# fonteechaveador2.net
KiCad netlist of a schematic drawn in EAGLE
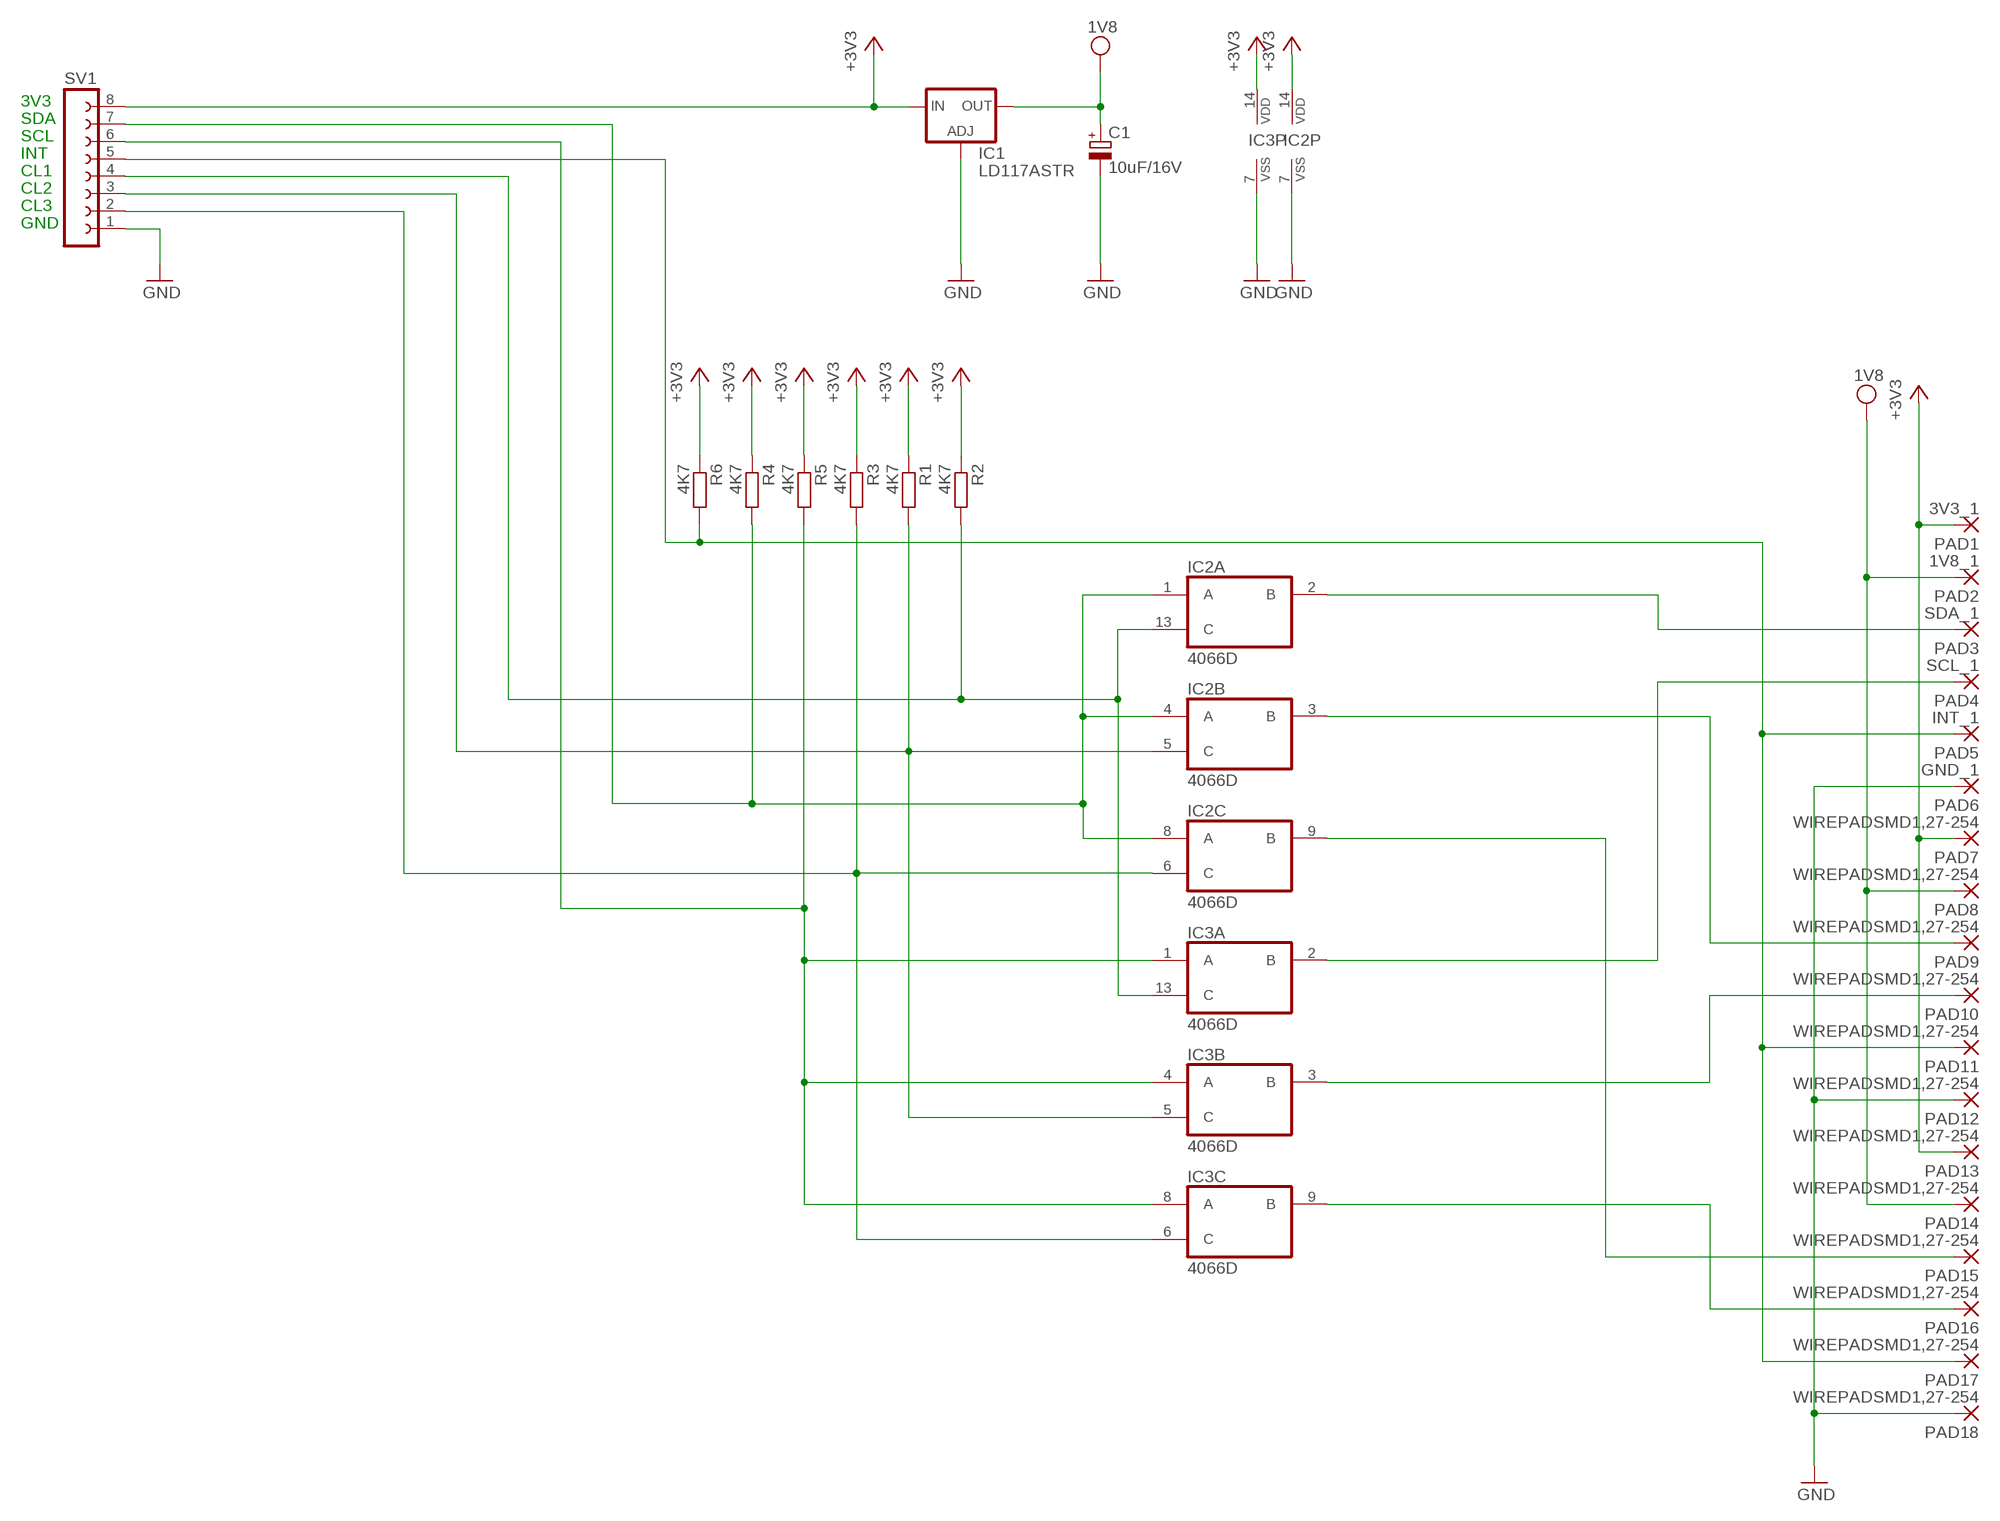
[diagram p0: schematic, sheet 1]

(export (version "E")
  (design (tool "Eeschema 10.0.6"))
  (components
    (comp (ref "C1")
      (value "10uF/16V")
      (footprint "eagle-import:140CLH-0810")
      (libsource (lib "eagle-import") (part "CPOL-EU140CLH-0810"))
    )
    (comp (ref "IC1")
      (value "LD117ASTR")
      (footprint "eagle-import:SOT223")
      (libsource (lib "eagle-import") (part "LD117A?STR"))
    )
    (comp (ref "IC2")
      (value "4066D")
      (footprint "eagle-import:SO14")
      (libsource (lib "eagle-import") (part "4066D"))
    )
    (comp (ref "IC3")
      (value "4066D")
      (footprint "eagle-import:SO14")
      (libsource (lib "eagle-import") (part "4066D"))
    )
    (comp (ref "PAD1")
      (value "3V3_1")
      (footprint "eagle-import:SMD1,27-2,54")
      (libsource (lib "eagle-import") (part "WIREPADSMD1,27-254"))
    )
    (comp (ref "PAD2")
      (value "1V8_1")
      (footprint "eagle-import:SMD1,27-2,54")
      (libsource (lib "eagle-import") (part "WIREPADSMD1,27-254"))
    )
    (comp (ref "PAD3")
      (value "SDA_1")
      (footprint "eagle-import:SMD1,27-2,54")
      (libsource (lib "eagle-import") (part "WIREPADSMD1,27-254"))
    )
    (comp (ref "PAD4")
      (value "SCL_1")
      (footprint "eagle-import:SMD1,27-2,54")
      (libsource (lib "eagle-import") (part "WIREPADSMD1,27-254"))
    )
    (comp (ref "PAD5")
      (value "INT_1")
      (footprint "eagle-import:SMD1,27-2,54")
      (libsource (lib "eagle-import") (part "WIREPADSMD1,27-254"))
    )
    (comp (ref "PAD6")
      (value "GND_1")
      (footprint "eagle-import:SMD1,27-2,54")
      (libsource (lib "eagle-import") (part "WIREPADSMD1,27-254"))
    )
    (comp (ref "PAD7")
      (value "WIREPADSMD1,27-254")
      (footprint "eagle-import:SMD1,27-2,54")
      (libsource (lib "eagle-import") (part "WIREPADSMD1,27-254"))
    )
    (comp (ref "PAD8")
      (value "WIREPADSMD1,27-254")
      (footprint "eagle-import:SMD1,27-2,54")
      (libsource (lib "eagle-import") (part "WIREPADSMD1,27-254"))
    )
    (comp (ref "PAD9")
      (value "WIREPADSMD1,27-254")
      (footprint "eagle-import:SMD1,27-2,54")
      (libsource (lib "eagle-import") (part "WIREPADSMD1,27-254"))
    )
    (comp (ref "PAD10")
      (value "WIREPADSMD1,27-254")
      (footprint "eagle-import:SMD1,27-2,54")
      (libsource (lib "eagle-import") (part "WIREPADSMD1,27-254"))
    )
    (comp (ref "PAD11")
      (value "WIREPADSMD1,27-254")
      (footprint "eagle-import:SMD1,27-2,54")
      (libsource (lib "eagle-import") (part "WIREPADSMD1,27-254"))
    )
    (comp (ref "PAD12")
      (value "WIREPADSMD1,27-254")
      (footprint "eagle-import:SMD1,27-2,54")
      (libsource (lib "eagle-import") (part "WIREPADSMD1,27-254"))
    )
    (comp (ref "PAD13")
      (value "WIREPADSMD1,27-254")
      (footprint "eagle-import:SMD1,27-2,54")
      (libsource (lib "eagle-import") (part "WIREPADSMD1,27-254"))
    )
    (comp (ref "PAD14")
      (value "WIREPADSMD1,27-254")
      (footprint "eagle-import:SMD1,27-2,54")
      (libsource (lib "eagle-import") (part "WIREPADSMD1,27-254"))
    )
    (comp (ref "PAD15")
      (value "WIREPADSMD1,27-254")
      (footprint "eagle-import:SMD1,27-2,54")
      (libsource (lib "eagle-import") (part "WIREPADSMD1,27-254"))
    )
    (comp (ref "PAD16")
      (value "WIREPADSMD1,27-254")
      (footprint "eagle-import:SMD1,27-2,54")
      (libsource (lib "eagle-import") (part "WIREPADSMD1,27-254"))
    )
    (comp (ref "PAD17")
      (value "WIREPADSMD1,27-254")
      (footprint "eagle-import:SMD1,27-2,54")
      (libsource (lib "eagle-import") (part "WIREPADSMD1,27-254"))
    )
    (comp (ref "PAD18")
      (value "WIREPADSMD1,27-254")
      (footprint "eagle-import:SMD1,27-2,54")
      (libsource (lib "eagle-import") (part "WIREPADSMD1,27-254"))
    )
    (comp (ref "R1")
      (value "4K7")
      (footprint "eagle-import:M0805")
      (libsource (lib "eagle-import") (part "R-EU_M0805"))
    )
    (comp (ref "R2")
      (value "4K7")
      (footprint "eagle-import:M0805")
      (libsource (lib "eagle-import") (part "R-EU_M0805"))
    )
    (comp (ref "R3")
      (value "4K7")
      (footprint "eagle-import:M0805")
      (libsource (lib "eagle-import") (part "R-EU_M0805"))
    )
    (comp (ref "R4")
      (value "4K7")
      (footprint "eagle-import:M0805")
      (libsource (lib "eagle-import") (part "R-EU_M0805"))
    )
    (comp (ref "R5")
      (value "4K7")
      (footprint "eagle-import:M0805")
      (libsource (lib "eagle-import") (part "R-EU_M0805"))
    )
    (comp (ref "R6")
      (value "4K7")
      (footprint "eagle-import:M0805")
      (libsource (lib "eagle-import") (part "R-EU_M0805"))
    )
    (comp (ref "SV1")
      (value "FE08-1")
      (footprint "eagle-import:FE08")
      (libsource (lib "eagle-import") (part "FE08-1"))
    )
  )
  (nets
    (net (code "1") (name "+3V3") (class "Default")
      (node (ref "IC1") (pin "3") (pinfunction "IN_3") (pintype "input"))
      (node (ref "IC2") (pin "14") (pinfunction "VDD_14") (pintype "power_in"))
      (node (ref "IC3") (pin "14") (pinfunction "VDD_14") (pintype "power_in"))
      (node (ref "PAD1") (pin "1") (pinfunction "P_1") (pintype "passive"))
      (node (ref "PAD13") (pin "1") (pinfunction "P_1") (pintype "passive"))
      (node (ref "PAD7") (pin "1") (pinfunction "P_1") (pintype "passive"))
      (node (ref "R1") (pin "1") (pinfunction "1_1") (pintype "passive"))
      (node (ref "R2") (pin "1") (pinfunction "1_1") (pintype "passive"))
      (node (ref "R3") (pin "1") (pinfunction "1_1") (pintype "passive"))
      (node (ref "R4") (pin "1") (pinfunction "1_1") (pintype "passive"))
      (node (ref "R5") (pin "1") (pinfunction "1_1") (pintype "passive"))
      (node (ref "R6") (pin "1") (pinfunction "1_1") (pintype "passive"))
      (node (ref "SV1") (pin "8") (pinfunction "8_8") (pintype "passive"))
    )
    (net (code "2") (name "1V8") (class "Default")
      (node (ref "C1") (pin "+") (pinfunction "+_+") (pintype "passive"))
      (node (ref "IC1") (pin "4") (pinfunction "OUT_4") (pintype "passive"))
      (node (ref "PAD14") (pin "1") (pinfunction "P_1") (pintype "passive"))
      (node (ref "PAD2") (pin "1") (pinfunction "P_1") (pintype "passive"))
      (node (ref "PAD8") (pin "1") (pinfunction "P_1") (pintype "passive"))
    )
    (net (code "3") (name "GND") (class "Default")
      (node (ref "C1") (pin "-") (pinfunction "-_-") (pintype "passive"))
      (node (ref "IC1") (pin "1") (pinfunction "ADJ_1") (pintype "input"))
      (node (ref "IC2") (pin "7") (pinfunction "VSS_7") (pintype "power_in"))
      (node (ref "IC3") (pin "7") (pinfunction "VSS_7") (pintype "power_in"))
      (node (ref "PAD12") (pin "1") (pinfunction "P_1") (pintype "passive"))
      (node (ref "PAD18") (pin "1") (pinfunction "P_1") (pintype "passive"))
      (node (ref "PAD6") (pin "1") (pinfunction "P_1") (pintype "passive"))
      (node (ref "SV1") (pin "1") (pinfunction "1_1") (pintype "passive"))
    )
    (net (code "4") (name "Net-(IC2A-A)") (class "Default")
      (node (ref "IC2") (pin "1") (pinfunction "A_1") (pintype "tri_state"))
      (node (ref "IC2") (pin "4") (pinfunction "A_4") (pintype "tri_state"))
      (node (ref "IC2") (pin "8") (pinfunction "A_8") (pintype "tri_state"))
      (node (ref "R4") (pin "2") (pinfunction "2_2") (pintype "passive"))
      (node (ref "SV1") (pin "7") (pinfunction "7_7") (pintype "passive"))
    )
    (net (code "5") (name "Net-(IC2A-B)") (class "Default")
      (node (ref "IC2") (pin "2") (pinfunction "B_2") (pintype "tri_state"))
      (node (ref "PAD3") (pin "1") (pinfunction "P_1") (pintype "passive"))
    )
    (net (code "6") (name "Net-(IC2A-C)") (class "Default")
      (node (ref "IC2") (pin "13") (pinfunction "C_13") (pintype "input"))
      (node (ref "IC3") (pin "13") (pinfunction "C_13") (pintype "input"))
      (node (ref "R2") (pin "2") (pinfunction "2_2") (pintype "passive"))
      (node (ref "SV1") (pin "4") (pinfunction "4_4") (pintype "passive"))
    )
    (net (code "7") (name "Net-(IC2B-B)") (class "Default")
      (node (ref "IC2") (pin "3") (pinfunction "B_3") (pintype "tri_state"))
      (node (ref "PAD9") (pin "1") (pinfunction "P_1") (pintype "passive"))
    )
    (net (code "8") (name "Net-(IC2B-C)") (class "Default")
      (node (ref "IC2") (pin "5") (pinfunction "C_5") (pintype "input"))
      (node (ref "IC3") (pin "5") (pinfunction "C_5") (pintype "input"))
      (node (ref "R1") (pin "2") (pinfunction "2_2") (pintype "passive"))
      (node (ref "SV1") (pin "3") (pinfunction "3_3") (pintype "passive"))
    )
    (net (code "9") (name "Net-(IC2C-B)") (class "Default")
      (node (ref "IC2") (pin "9") (pinfunction "B_9") (pintype "tri_state"))
      (node (ref "PAD15") (pin "1") (pinfunction "P_1") (pintype "passive"))
    )
    (net (code "10") (name "Net-(IC2C-C)") (class "Default")
      (node (ref "IC2") (pin "6") (pinfunction "C_6") (pintype "input"))
      (node (ref "IC3") (pin "6") (pinfunction "C_6") (pintype "input"))
      (node (ref "R3") (pin "2") (pinfunction "2_2") (pintype "passive"))
      (node (ref "SV1") (pin "2") (pinfunction "2_2") (pintype "passive"))
    )
    (net (code "11") (name "Net-(IC3A-A)") (class "Default")
      (node (ref "IC3") (pin "1") (pinfunction "A_1") (pintype "tri_state"))
      (node (ref "IC3") (pin "4") (pinfunction "A_4") (pintype "tri_state"))
      (node (ref "IC3") (pin "8") (pinfunction "A_8") (pintype "tri_state"))
      (node (ref "R5") (pin "2") (pinfunction "2_2") (pintype "passive"))
      (node (ref "SV1") (pin "6") (pinfunction "6_6") (pintype "passive"))
    )
    (net (code "12") (name "Net-(IC3A-B)") (class "Default")
      (node (ref "IC3") (pin "2") (pinfunction "B_2") (pintype "tri_state"))
      (node (ref "PAD4") (pin "1") (pinfunction "P_1") (pintype "passive"))
    )
    (net (code "13") (name "Net-(IC3B-B)") (class "Default")
      (node (ref "IC3") (pin "3") (pinfunction "B_3") (pintype "tri_state"))
      (node (ref "PAD10") (pin "1") (pinfunction "P_1") (pintype "passive"))
    )
    (net (code "14") (name "Net-(IC3C-B)") (class "Default")
      (node (ref "IC3") (pin "9") (pinfunction "B_9") (pintype "tri_state"))
      (node (ref "PAD16") (pin "1") (pinfunction "P_1") (pintype "passive"))
    )
    (net (code "15") (name "Net-(PAD11-P)") (class "Default")
      (node (ref "PAD11") (pin "1") (pinfunction "P_1") (pintype "passive"))
      (node (ref "PAD17") (pin "1") (pinfunction "P_1") (pintype "passive"))
      (node (ref "PAD5") (pin "1") (pinfunction "P_1") (pintype "passive"))
      (node (ref "R6") (pin "2") (pinfunction "2_2") (pintype "passive"))
      (node (ref "SV1") (pin "5") (pinfunction "5_5") (pintype "passive"))
    )
  )
)
